# HLM1_Outsourced_V2.net
KiCad netlist of a schematic drawn in EAGLE
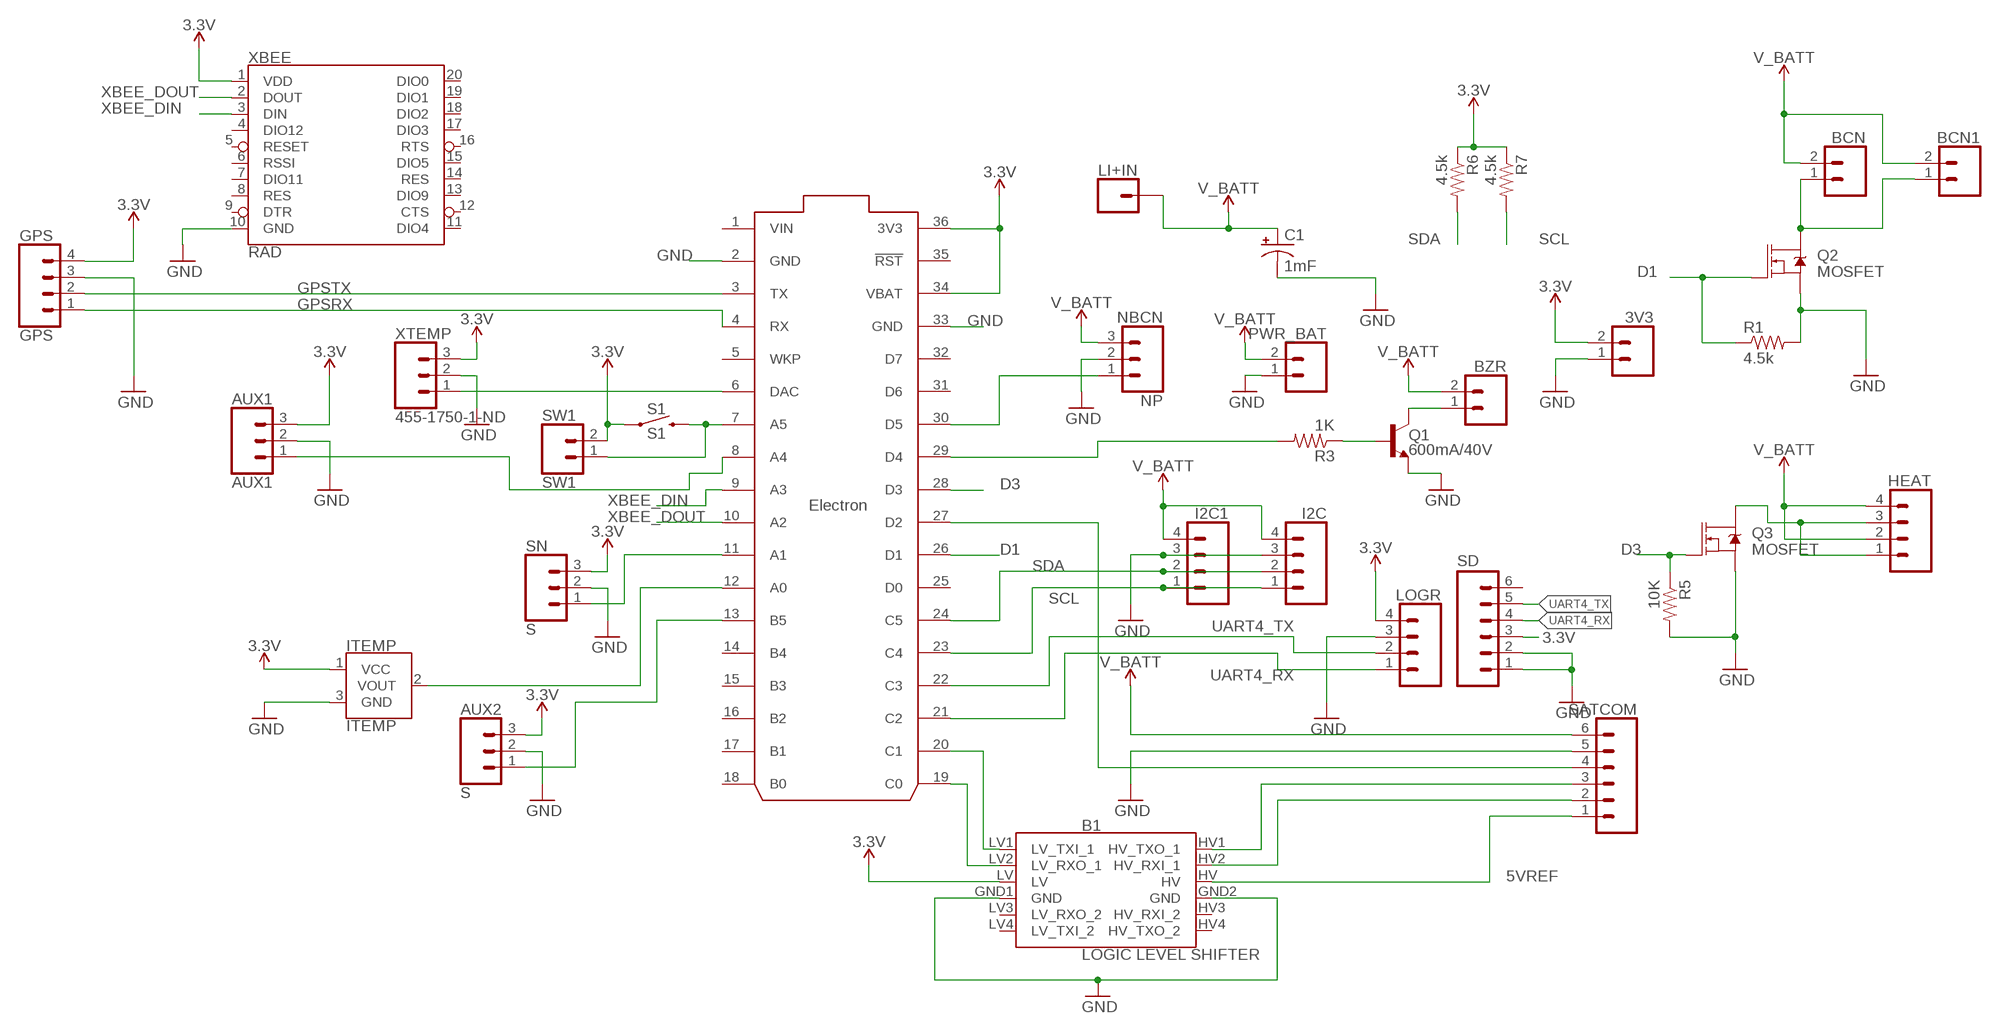
[diagram p0: schematic, sheet 1]

(export (version "E")
  (design (tool "Eeschema 10.0.6"))
  (components
    (comp (ref "3V3")
      (value "CONN_02")
      (footprint "eagle-import:1X02")
      (libsource (lib "eagle-import") (part "CONN_02"))
    )
    (comp (ref "AUX1")
      (value "AUX1")
      (footprint "eagle-import:1X03")
      (libsource (lib "eagle-import") (part "CONN_03"))
    )
    (comp (ref "AUX2")
      (value "S")
      (footprint "eagle-import:1X03")
      (libsource (lib "eagle-import") (part "CONN_03"))
    )
    (comp (ref "B1")
      (value "LOGIC LEVEL SHIFTER")
      (footprint "eagle-import:SPARKFUN_LOGIC_LEVEL_CONVERTER")
      (libsource (lib "eagle-import") (part "SPARKFUN_LOGIC_LEVEL_CONVERTER"))
    )
    (comp (ref "BCN")
      (value "CONN_02")
      (footprint "eagle-import:1X02")
      (libsource (lib "eagle-import") (part "CONN_02"))
    )
    (comp (ref "BCN1")
      (value "CONN_02")
      (footprint "eagle-import:1X02")
      (libsource (lib "eagle-import") (part "CONN_02"))
    )
    (comp (ref "BZR")
      (value "CONN_02")
      (footprint "eagle-import:1X02")
      (libsource (lib "eagle-import") (part "CONN_02"))
    )
    (comp (ref "C1")
      (value "1mF")
      (footprint "eagle-import:CPOL-RADIAL-5MM-10MM")
      (libsource (lib "eagle-import") (part "1000UF-RADIAL-5MM-25V-20%"))
    )
    (comp (ref "GPS")
      (value "GPS")
      (footprint "eagle-import:1X04")
      (libsource (lib "eagle-import") (part "CONN_04"))
    )
    (comp (ref "HEAT")
      (value "CONN_04")
      (footprint "eagle-import:1X04")
      (libsource (lib "eagle-import") (part "CONN_04"))
    )
    (comp (ref "I2C")
      (value "CONN_04")
      (footprint "eagle-import:1X04")
      (libsource (lib "eagle-import") (part "CONN_04"))
    )
    (comp (ref "I2C1")
      (value "CONN_04")
      (footprint "eagle-import:1X04")
      (libsource (lib "eagle-import") (part "CONN_04"))
    )
    (comp (ref "ITEMP")
      (value "ITEMP")
      (footprint "eagle-import:TO-92")
      (libsource (lib "eagle-import") (part "TMP36GT9"))
    )
    (comp (ref "LI+IN")
      (value "CONN_01")
      (footprint "eagle-import:1X01")
      (libsource (lib "eagle-import") (part "CONN_01"))
    )
    (comp (ref "LOGR")
      (value "CONN_04")
      (footprint "eagle-import:1X04")
      (libsource (lib "eagle-import") (part "CONN_04"))
    )
    (comp (ref "MCU")
      (value "ELECTRON")
      (footprint "eagle-import:ELECTRON")
      (libsource (lib "eagle-import") (part "ELECTRON_WITH_HEADERS"))
    )
    (comp (ref "NBCN")
      (value "NP")
      (footprint "eagle-import:1X03")
      (libsource (lib "eagle-import") (part "CONN_03"))
    )
    (comp (ref "PWR_BAT")
      (value "CONN_02")
      (footprint "eagle-import:1X02")
      (libsource (lib "eagle-import") (part "CONN_02"))
    )
    (comp (ref "Q1")
      (value "600mA/40V")
      (footprint "eagle-import:TO-92")
      (libsource (lib "eagle-import") (part "TRANS_NPN-P2N2222A"))
    )
    (comp (ref "Q2")
      (value "MOSFET")
      (footprint "eagle-import:TO220V")
      (libsource (lib "eagle-import") (part "MOSFET-NCH-FQP30N06L"))
    )
    (comp (ref "Q3")
      (value "MOSFET")
      (footprint "eagle-import:TO220V")
      (libsource (lib "eagle-import") (part "MOSFET-NCH-FQP30N06L"))
    )
    (comp (ref "R1")
      (value "4.5k")
      (footprint "eagle-import:1_6W-RES")
      (libsource (lib "eagle-import") (part "RESISTORPTH-1/6W"))
    )
    (comp (ref "R3")
      (value "1K")
      (footprint "eagle-import:1_6W-RES")
      (libsource (lib "eagle-import") (part "RESISTORPTH-1/6W"))
    )
    (comp (ref "R5")
      (value "10K")
      (footprint "eagle-import:1_6W-RES")
      (libsource (lib "eagle-import") (part "RESISTORPTH-1/6W"))
    )
    (comp (ref "R6")
      (value "4.5k")
      (footprint "eagle-import:1_6W-RES")
      (libsource (lib "eagle-import") (part "RESISTORPTH-1/6W"))
    )
    (comp (ref "R7")
      (value "4.5k")
      (footprint "eagle-import:1_6W-RES")
      (libsource (lib "eagle-import") (part "RESISTORPTH-1/6W"))
    )
    (comp (ref "S1")
      (value "S1")
      (footprint "eagle-import:TACTILE_SWITCH_PTH_6.0MM")
      (libsource (lib "eagle-import") (part "MOMENTARY-SWITCH-SPST-PTH-6.0MM"))
    )
    (comp (ref "SATCOM")
      (value "CONN_06SILK_FEMALE_PTH")
      (footprint "eagle-import:1X06@1")
      (libsource (lib "eagle-import") (part "CONN_06SILK_FEMALE_PTH"))
    )
    (comp (ref "SD")
      (value "M06NO_SILK_FEMALE_PTH")
      (footprint "eagle-import:1X06_NO_SILK")
      (libsource (lib "eagle-import") (part "M06NO_SILK_FEMALE_PTH"))
    )
    (comp (ref "SN")
      (value "S")
      (footprint "eagle-import:1X03")
      (libsource (lib "eagle-import") (part "CONN_03"))
    )
    (comp (ref "SW1")
      (value "SW1")
      (footprint "eagle-import:1X02")
      (libsource (lib "eagle-import") (part "CONN_02"))
    )
    (comp (ref "XBEE")
      (value "RAD")
      (footprint "eagle-import:XBEE-LONGPAD")
      (libsource (lib "eagle-import") (part "XBEELONGPAD"))
    )
    (comp (ref "XTEMP")
      (value "455-1750-1-ND")
      (footprint "eagle-import:1X03")
      (libsource (lib "eagle-import") (part "CONN_03"))
    )
  )
  (nets
    (net (code "1") (name "/5VREF") (class "Default")
      (node (ref "B1") (pin "HV") (pinfunction "HV_HV") (pintype "power_in"))
      (node (ref "SATCOM") (pin "1") (pinfunction "1_1") (pintype "passive"))
    )
    (net (code "2") (name "/D1") (class "Default")
      (node (ref "MCU") (pin "26") (pinfunction "D1_26") (pintype "bidirectional"))
      (node (ref "Q2") (pin "1") (pinfunction "G_1") (pintype "bidirectional"))
      (node (ref "R1") (pin "1") (pinfunction "1_1") (pintype "passive"))
    )
    (net (code "3") (name "/D3") (class "Default")
      (node (ref "MCU") (pin "28") (pinfunction "D3_28") (pintype "bidirectional"))
      (node (ref "Q3") (pin "1") (pinfunction "G_1") (pintype "bidirectional"))
      (node (ref "R5") (pin "1") (pinfunction "1_1") (pintype "passive"))
    )
    (net (code "4") (name "/GPSRX") (class "Default")
      (node (ref "GPS") (pin "1") (pinfunction "1_1") (pintype "passive"))
      (node (ref "MCU") (pin "4") (pinfunction "RX_4") (pintype "bidirectional"))
    )
    (net (code "5") (name "/GPSTX") (class "Default")
      (node (ref "GPS") (pin "2") (pinfunction "2_2") (pintype "passive"))
      (node (ref "MCU") (pin "3") (pinfunction "TX_3") (pintype "bidirectional"))
    )
    (net (code "6") (name "/SCL") (class "Default")
      (node (ref "I2C") (pin "1") (pinfunction "1_1") (pintype "passive"))
      (node (ref "I2C1") (pin "1") (pinfunction "1_1") (pintype "passive"))
      (node (ref "MCU") (pin "23") (pinfunction "C4_23") (pintype "bidirectional"))
      (node (ref "R7") (pin "2") (pinfunction "2_2") (pintype "passive"))
    )
    (net (code "7") (name "/SDA") (class "Default")
      (node (ref "I2C") (pin "2") (pinfunction "2_2") (pintype "passive"))
      (node (ref "I2C1") (pin "2") (pinfunction "2_2") (pintype "passive"))
      (node (ref "MCU") (pin "24") (pinfunction "C5_24") (pintype "bidirectional"))
      (node (ref "R6") (pin "2") (pinfunction "2_2") (pintype "passive"))
    )
    (net (code "8") (name "/VIN") (class "Default")
      (node (ref "MCU") (pin "1") (pinfunction "VIN_1") (pintype "power_in"))
    )
    (net (code "9") (name "/XBEE_DIN") (class "Default")
      (node (ref "MCU") (pin "9") (pinfunction "A3_9") (pintype "bidirectional"))
      (node (ref "XBEE") (pin "3") (pinfunction "DIN_3") (pintype "input"))
    )
    (net (code "10") (name "/XBEE_DOUT") (class "Default")
      (node (ref "MCU") (pin "10") (pinfunction "A2_10") (pintype "bidirectional"))
      (node (ref "XBEE") (pin "2") (pinfunction "DOUT_2") (pintype "output"))
    )
    (net (code "11") (name "3.3V") (class "Default")
      (node (ref "3V3") (pin "2") (pinfunction "2_2") (pintype "passive"))
      (node (ref "AUX1") (pin "3") (pinfunction "3_3") (pintype "passive"))
      (node (ref "AUX2") (pin "3") (pinfunction "3_3") (pintype "passive"))
      (node (ref "B1") (pin "LV") (pinfunction "LV_LV") (pintype "power_in"))
      (node (ref "GPS") (pin "4") (pinfunction "4_4") (pintype "passive"))
      (node (ref "ITEMP") (pin "1") (pinfunction "VCC_1") (pintype "bidirectional"))
      (node (ref "LOGR") (pin "4") (pinfunction "4_4") (pintype "passive"))
      (node (ref "MCU") (pin "34") (pinfunction "VBAT_34") (pintype "power_in"))
      (node (ref "MCU") (pin "36") (pinfunction "3V3_36") (pintype "power_in"))
      (node (ref "R6") (pin "1") (pinfunction "1_1") (pintype "passive"))
      (node (ref "R7") (pin "1") (pinfunction "1_1") (pintype "passive"))
      (node (ref "S1") (pin "1") (pinfunction "1_1") (pintype "passive"))
      (node (ref "SD") (pin "3") (pinfunction "3_3") (pintype "passive"))
      (node (ref "SN") (pin "3") (pinfunction "3_3") (pintype "passive"))
      (node (ref "SW1") (pin "2") (pinfunction "2_2") (pintype "passive"))
      (node (ref "XBEE") (pin "1") (pinfunction "VDD_1") (pintype "power_in"))
      (node (ref "XTEMP") (pin "3") (pinfunction "3_3") (pintype "passive"))
    )
    (net (code "12") (name "GND") (class "Default")
      (node (ref "3V3") (pin "1") (pinfunction "1_1") (pintype "passive"))
      (node (ref "AUX1") (pin "2") (pinfunction "2_2") (pintype "passive"))
      (node (ref "AUX2") (pin "2") (pinfunction "2_2") (pintype "passive"))
      (node (ref "B1") (pin "GND1") (pinfunction "GND_GND1") (pintype "power_in"))
      (node (ref "B1") (pin "GND2") (pinfunction "GND_GND2") (pintype "power_in"))
      (node (ref "C1") (pin "-") (pinfunction "-_-") (pintype "passive"))
      (node (ref "GPS") (pin "3") (pinfunction "3_3") (pintype "passive"))
      (node (ref "I2C") (pin "3") (pinfunction "3_3") (pintype "passive"))
      (node (ref "I2C1") (pin "3") (pinfunction "3_3") (pintype "passive"))
      (node (ref "ITEMP") (pin "3") (pinfunction "GND_3") (pintype "bidirectional"))
      (node (ref "LOGR") (pin "3") (pinfunction "3_3") (pintype "passive"))
      (node (ref "MCU") (pin "2") (pinfunction "GND_2") (pintype "power_in"))
      (node (ref "MCU") (pin "33") (pinfunction "GND_33") (pintype "power_in"))
      (node (ref "NBCN") (pin "2") (pinfunction "2_2") (pintype "passive"))
      (node (ref "PWR_BAT") (pin "1") (pinfunction "1_1") (pintype "passive"))
      (node (ref "Q1") (pin "3") (pinfunction "E_3") (pintype "passive"))
      (node (ref "Q2") (pin "3") (pinfunction "S_3") (pintype "bidirectional"))
      (node (ref "Q3") (pin "3") (pinfunction "S_3") (pintype "bidirectional"))
      (node (ref "R1") (pin "2") (pinfunction "2_2") (pintype "passive"))
      (node (ref "R5") (pin "2") (pinfunction "2_2") (pintype "passive"))
      (node (ref "SATCOM") (pin "5") (pinfunction "5_5") (pintype "passive"))
      (node (ref "SD") (pin "1") (pinfunction "1_1") (pintype "passive"))
      (node (ref "SD") (pin "2") (pinfunction "2_2") (pintype "passive"))
      (node (ref "SN") (pin "2") (pinfunction "2_2") (pintype "passive"))
      (node (ref "XBEE") (pin "10") (pinfunction "GND_10") (pintype "power_in"))
      (node (ref "XTEMP") (pin "2") (pinfunction "2_2") (pintype "passive"))
    )
    (net (code "13") (name "Net-(B1-HV_RXI_1)") (class "Default")
      (node (ref "B1") (pin "HV2") (pinfunction "HV_RXI_1_HV2") (pintype "bidirectional"))
      (node (ref "SATCOM") (pin "2") (pinfunction "2_2") (pintype "passive"))
    )
    (net (code "14") (name "Net-(B1-HV_TXO_1)") (class "Default")
      (node (ref "B1") (pin "HV1") (pinfunction "HV_TXO_1_HV1") (pintype "bidirectional"))
      (node (ref "SATCOM") (pin "3") (pinfunction "3_3") (pintype "passive"))
    )
    (net (code "15") (name "Net-(B1-LV_RXO_1)") (class "Default")
      (node (ref "B1") (pin "LV2") (pinfunction "LV_RXO_1_LV2") (pintype "bidirectional"))
      (node (ref "MCU") (pin "19") (pinfunction "C0_19") (pintype "bidirectional"))
    )
    (net (code "16") (name "Net-(B1-LV_TXI_1)") (class "Default")
      (node (ref "B1") (pin "LV1") (pinfunction "LV_TXI_1_LV1") (pintype "bidirectional"))
      (node (ref "MCU") (pin "20") (pinfunction "C1_20") (pintype "bidirectional"))
    )
    (net (code "17") (name "Net-(ITEMP-VOUT)") (class "Default")
      (node (ref "ITEMP") (pin "2") (pinfunction "VOUT_2") (pintype "bidirectional"))
      (node (ref "MCU") (pin "12") (pinfunction "A0_12") (pintype "bidirectional"))
    )
    (net (code "18") (name "Net-(MCU-A1)") (class "Default")
      (node (ref "MCU") (pin "11") (pinfunction "A1_11") (pintype "bidirectional"))
      (node (ref "SN") (pin "1") (pinfunction "1_1") (pintype "passive"))
    )
    (net (code "19") (name "Net-(MCU-A4)") (class "Default")
      (node (ref "AUX1") (pin "1") (pinfunction "1_1") (pintype "passive"))
      (node (ref "MCU") (pin "8") (pinfunction "A4_8") (pintype "bidirectional"))
    )
    (net (code "20") (name "Net-(MCU-A5)") (class "Default")
      (node (ref "MCU") (pin "7") (pinfunction "A5_7") (pintype "bidirectional"))
      (node (ref "S1") (pin "3") (pinfunction "2_3") (pintype "passive"))
      (node (ref "SW1") (pin "1") (pinfunction "1_1") (pintype "passive"))
    )
    (net (code "21") (name "Net-(MCU-B5)") (class "Default")
      (node (ref "AUX2") (pin "1") (pinfunction "1_1") (pintype "passive"))
      (node (ref "MCU") (pin "13") (pinfunction "B5_13") (pintype "bidirectional"))
    )
    (net (code "22") (name "Net-(MCU-D2)") (class "Default")
      (node (ref "MCU") (pin "27") (pinfunction "D2_27") (pintype "bidirectional"))
      (node (ref "SATCOM") (pin "4") (pinfunction "4_4") (pintype "passive"))
    )
    (net (code "23") (name "Net-(MCU-D4)") (class "Default")
      (node (ref "MCU") (pin "29") (pinfunction "D4_29") (pintype "bidirectional"))
      (node (ref "R3") (pin "2") (pinfunction "2_2") (pintype "passive"))
    )
    (net (code "24") (name "Net-(MCU-D5)") (class "Default")
      (node (ref "MCU") (pin "30") (pinfunction "D5_30") (pintype "bidirectional"))
      (node (ref "NBCN") (pin "1") (pinfunction "1_1") (pintype "passive"))
    )
    (net (code "25") (name "Net-(MCU-DAC)") (class "Default")
      (node (ref "MCU") (pin "6") (pinfunction "DAC_6") (pintype "bidirectional"))
      (node (ref "XTEMP") (pin "1") (pinfunction "1_1") (pintype "passive"))
    )
    (net (code "26") (name "Net-(Q1-B)") (class "Default")
      (node (ref "Q1") (pin "2") (pinfunction "B_2") (pintype "passive"))
      (node (ref "R3") (pin "1") (pinfunction "1_1") (pintype "passive"))
    )
    (net (code "27") (name "Net-(Q1-C)") (class "Default")
      (node (ref "BZR") (pin "1") (pinfunction "1_1") (pintype "passive"))
      (node (ref "Q1") (pin "1") (pinfunction "C_1") (pintype "passive"))
    )
    (net (code "28") (name "Net-(Q2-D)") (class "Default")
      (node (ref "BCN") (pin "1") (pinfunction "1_1") (pintype "passive"))
      (node (ref "BCN1") (pin "1") (pinfunction "1_1") (pintype "passive"))
      (node (ref "Q2") (pin "2") (pinfunction "D_2") (pintype "bidirectional"))
    )
    (net (code "29") (name "Net-(Q3-D)") (class "Default")
      (node (ref "HEAT") (pin "1") (pinfunction "1_1") (pintype "passive"))
      (node (ref "HEAT") (pin "3") (pinfunction "3_3") (pintype "passive"))
      (node (ref "Q3") (pin "2") (pinfunction "D_2") (pintype "bidirectional"))
    )
    (net (code "30") (name "UART4_RX") (class "Default")
      (node (ref "LOGR") (pin "1") (pinfunction "1_1") (pintype "passive"))
      (node (ref "MCU") (pin "21") (pinfunction "C2_21") (pintype "bidirectional"))
      (node (ref "SD") (pin "4") (pinfunction "4_4") (pintype "passive"))
    )
    (net (code "31") (name "UART4_TX") (class "Default")
      (node (ref "LOGR") (pin "2") (pinfunction "2_2") (pintype "passive"))
      (node (ref "MCU") (pin "22") (pinfunction "C3_22") (pintype "bidirectional"))
      (node (ref "SD") (pin "5") (pinfunction "5_5") (pintype "passive"))
    )
    (net (code "32") (name "V_BATT") (class "Default")
      (node (ref "BCN") (pin "2") (pinfunction "2_2") (pintype "passive"))
      (node (ref "BCN1") (pin "2") (pinfunction "2_2") (pintype "passive"))
      (node (ref "BZR") (pin "2") (pinfunction "2_2") (pintype "passive"))
      (node (ref "C1") (pin "+") (pinfunction "+_+") (pintype "passive"))
      (node (ref "HEAT") (pin "2") (pinfunction "2_2") (pintype "passive"))
      (node (ref "HEAT") (pin "4") (pinfunction "4_4") (pintype "passive"))
      (node (ref "I2C") (pin "4") (pinfunction "4_4") (pintype "passive"))
      (node (ref "I2C1") (pin "4") (pinfunction "4_4") (pintype "passive"))
      (node (ref "LI+IN") (pin "1") (pinfunction "1_1") (pintype "passive"))
      (node (ref "NBCN") (pin "3") (pinfunction "3_3") (pintype "passive"))
      (node (ref "PWR_BAT") (pin "2") (pinfunction "2_2") (pintype "passive"))
      (node (ref "SATCOM") (pin "6") (pinfunction "6_6") (pintype "passive"))
    )
    (net (code "33") (name "unconnected-(B1-HV_RXI_2-PadHV3)") (class "Default")
      (node (ref "B1") (pin "HV3") (pinfunction "HV_RXI_2_HV3") (pintype "bidirectional"))
    )
    (net (code "34") (name "unconnected-(B1-HV_TXO_2-PadHV4)") (class "Default")
      (node (ref "B1") (pin "HV4") (pinfunction "HV_TXO_2_HV4") (pintype "bidirectional"))
    )
    (net (code "35") (name "unconnected-(B1-LV_RXO_2-PadLV3)") (class "Default")
      (node (ref "B1") (pin "LV3") (pinfunction "LV_RXO_2_LV3") (pintype "bidirectional"))
    )
    (net (code "36") (name "unconnected-(B1-LV_TXI_2-PadLV4)") (class "Default")
      (node (ref "B1") (pin "LV4") (pinfunction "LV_TXI_2_LV4") (pintype "bidirectional"))
    )
    (net (code "37") (name "unconnected-(MCU-B0-Pad18)") (class "Default")
      (node (ref "MCU") (pin "18") (pinfunction "B0_18") (pintype "bidirectional"))
    )
    (net (code "38") (name "unconnected-(MCU-B1-Pad17)") (class "Default")
      (node (ref "MCU") (pin "17") (pinfunction "B1_17") (pintype "bidirectional"))
    )
    (net (code "39") (name "unconnected-(MCU-B2-Pad16)") (class "Default")
      (node (ref "MCU") (pin "16") (pinfunction "B2_16") (pintype "bidirectional"))
    )
    (net (code "40") (name "unconnected-(MCU-B3-Pad15)") (class "Default")
      (node (ref "MCU") (pin "15") (pinfunction "B3_15") (pintype "bidirectional"))
    )
    (net (code "41") (name "unconnected-(MCU-B4-Pad14)") (class "Default")
      (node (ref "MCU") (pin "14") (pinfunction "B4_14") (pintype "bidirectional"))
    )
    (net (code "42") (name "unconnected-(MCU-D0-Pad25)") (class "Default")
      (node (ref "MCU") (pin "25") (pinfunction "D0_25") (pintype "bidirectional"))
    )
    (net (code "43") (name "unconnected-(MCU-D6-Pad31)") (class "Default")
      (node (ref "MCU") (pin "31") (pinfunction "D6_31") (pintype "bidirectional"))
    )
    (net (code "44") (name "unconnected-(MCU-D7-Pad32)") (class "Default")
      (node (ref "MCU") (pin "32") (pinfunction "D7_32") (pintype "bidirectional"))
    )
    (net (code "45") (name "unconnected-(MCU-WKP-Pad5)") (class "Default")
      (node (ref "MCU") (pin "5") (pinfunction "WKP_5") (pintype "bidirectional"))
    )
    (net (code "46") (name "unconnected-(MCU-~{RST}-Pad35)") (class "Default")
      (node (ref "MCU") (pin "35") (pinfunction "~{RST}_35") (pintype "bidirectional"))
    )
    (net (code "47") (name "unconnected-(SD-Pad6)") (class "Default")
      (node (ref "SD") (pin "6") (pinfunction "6_6") (pintype "passive"))
    )
    (net (code "48") (name "unconnected-(XBEE-CTS-Pad12)") (class "Default")
      (node (ref "XBEE") (pin "12") (pinfunction "CTS_12") (pintype "output"))
    )
    (net (code "49") (name "unconnected-(XBEE-DIO0-Pad20)") (class "Default")
      (node (ref "XBEE") (pin "20") (pinfunction "DIO0_20") (pintype "bidirectional"))
    )
    (net (code "50") (name "unconnected-(XBEE-DIO1-Pad19)") (class "Default")
      (node (ref "XBEE") (pin "19") (pinfunction "DIO1_19") (pintype "bidirectional"))
    )
    (net (code "51") (name "unconnected-(XBEE-DIO2-Pad18)") (class "Default")
      (node (ref "XBEE") (pin "18") (pinfunction "DIO2_18") (pintype "bidirectional"))
    )
    (net (code "52") (name "unconnected-(XBEE-DIO3-Pad17)") (class "Default")
      (node (ref "XBEE") (pin "17") (pinfunction "DIO3_17") (pintype "bidirectional"))
    )
    (net (code "53") (name "unconnected-(XBEE-DIO4-Pad11)") (class "Default")
      (node (ref "XBEE") (pin "11") (pinfunction "DIO4_11") (pintype "bidirectional"))
    )
    (net (code "54") (name "unconnected-(XBEE-DIO5-Pad15)") (class "Default")
      (node (ref "XBEE") (pin "15") (pinfunction "DIO5_15") (pintype "bidirectional"))
    )
    (net (code "55") (name "unconnected-(XBEE-DIO9-Pad13)") (class "Default")
      (node (ref "XBEE") (pin "13") (pinfunction "DIO9_13") (pintype "bidirectional"))
    )
    (net (code "56") (name "unconnected-(XBEE-DIO11-Pad7)") (class "Default")
      (node (ref "XBEE") (pin "7") (pinfunction "DIO11_7") (pintype "bidirectional"))
    )
    (net (code "57") (name "unconnected-(XBEE-DIO12-Pad4)") (class "Default")
      (node (ref "XBEE") (pin "4") (pinfunction "DIO12_4") (pintype "bidirectional"))
    )
    (net (code "58") (name "unconnected-(XBEE-DTR-Pad9)") (class "Default")
      (node (ref "XBEE") (pin "9") (pinfunction "DTR_9") (pintype "bidirectional"))
    )
    (net (code "59") (name "unconnected-(XBEE-RES-Pad8)") (class "Default")
      (node (ref "XBEE") (pin "8") (pinfunction "RES_8") (pintype "bidirectional"))
    )
    (net (code "60") (name "unconnected-(XBEE-RES-Pad14)") (class "Default")
      (node (ref "XBEE") (pin "14") (pinfunction "RES_14") (pintype "bidirectional"))
    )
    (net (code "61") (name "unconnected-(XBEE-RESET-Pad5)") (class "Default")
      (node (ref "XBEE") (pin "5") (pinfunction "RESET_5") (pintype "input"))
    )
    (net (code "62") (name "unconnected-(XBEE-RSSI-Pad6)") (class "Default")
      (node (ref "XBEE") (pin "6") (pinfunction "RSSI_6") (pintype "bidirectional"))
    )
    (net (code "63") (name "unconnected-(XBEE-RTS-Pad16)") (class "Default")
      (node (ref "XBEE") (pin "16") (pinfunction "RTS_16") (pintype "input"))
    )
  )
)
